# pcb-jetson.net
KiCad netlist of a schematic drawn in EAGLE
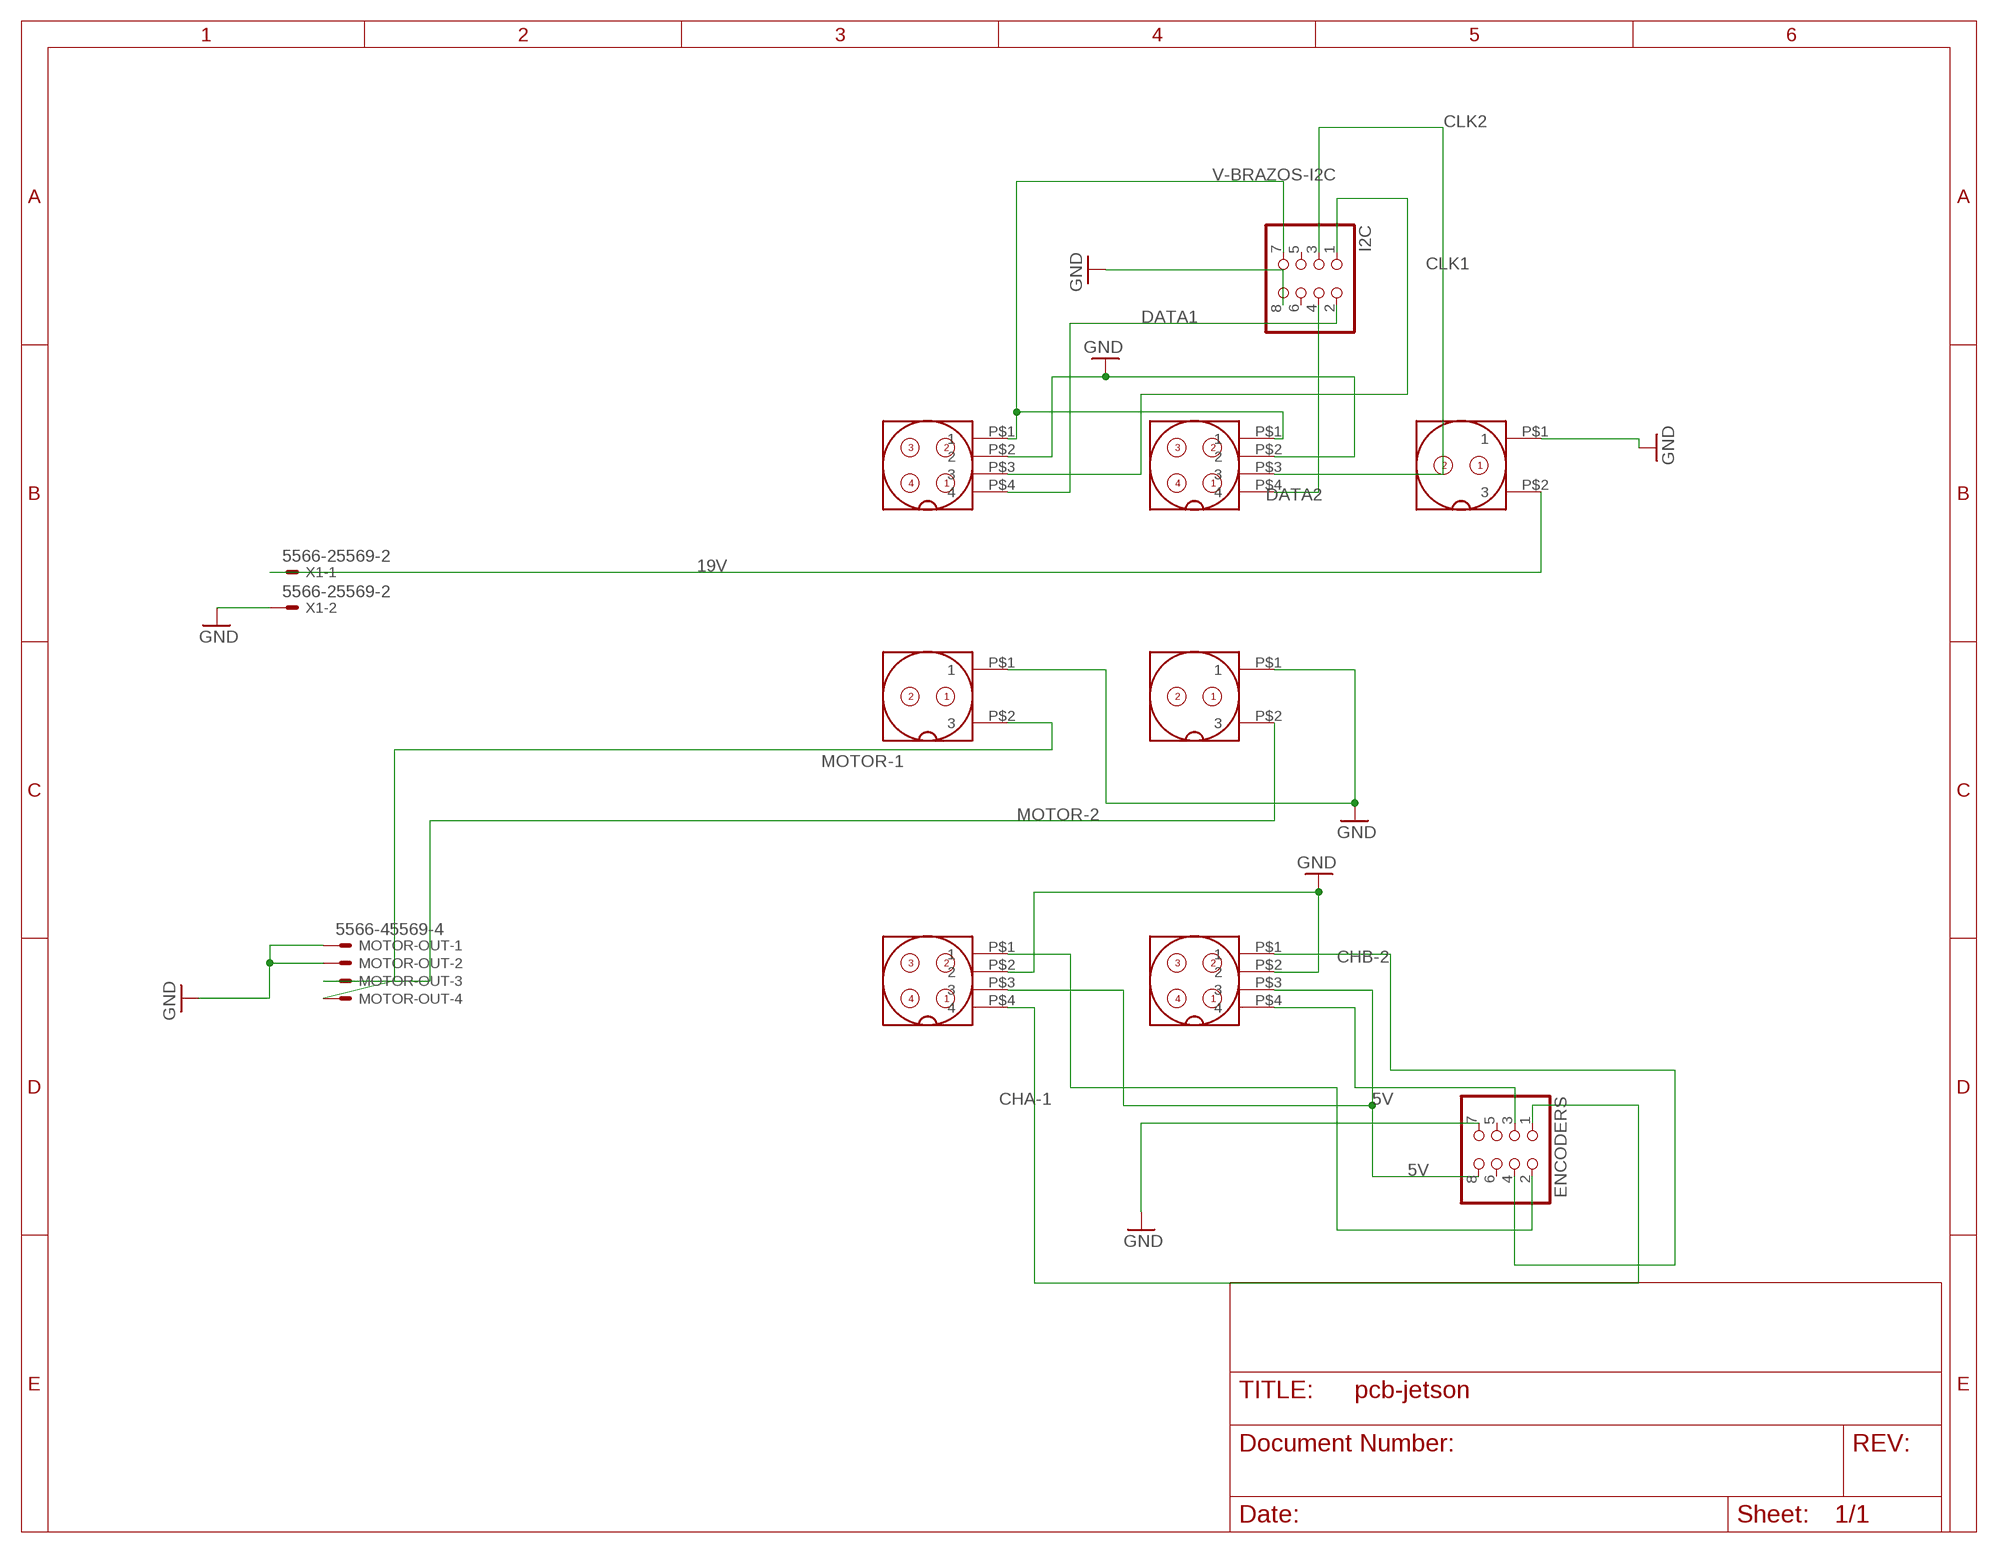
[diagram p0: schematic, sheet 1]

(export (version "E")
  (design (tool "Eeschema 10.0.6"))
  (components
    (comp (ref "BRAZO-I2C-2")
      (value "GX16_4_PINS")
      (footprint "eagle-import:GX16_4_PINS_PADS")
      (libsource (lib "eagle-import") (part "GX16_4_PINS"))
    )
    (comp (ref "BRAZO_I2C-1")
      (value "GX16_4_PINS")
      (footprint "eagle-import:GX16_4_PINS_PADS")
      (libsource (lib "eagle-import") (part "GX16_4_PINS"))
    )
    (comp (ref "ENCODERS")
      (value "PINHD-2X4")
      (footprint "eagle-import:2X04")
      (libsource (lib "eagle-import") (part "PINHD-2X4"))
    )
    (comp (ref "I2C")
      (value "PINHD-2X4")
      (footprint "eagle-import:2X04")
      (libsource (lib "eagle-import") (part "PINHD-2X4"))
    )
    (comp (ref "JETSONIN")
      (value "GX16_2_PINS")
      (footprint "eagle-import:GX16_2_PINS_PADS")
      (libsource (lib "eagle-import") (part "GX16_2_PINS"))
    )
    (comp (ref "MOTOR-OUT")
      (value "5566-45569-4")
      (footprint "eagle-import:5569-4")
      (libsource (lib "eagle-import") (part "5566-45569-4"))
    )
    (comp (ref "MOTOR1")
      (value "GX16_2_PINS")
      (footprint "eagle-import:GX16_2_PINS_PADS")
      (libsource (lib "eagle-import") (part "GX16_2_PINS"))
    )
    (comp (ref "MOTOR2")
      (value "GX16_2_PINS")
      (footprint "eagle-import:GX16_2_PINS_PADS")
      (libsource (lib "eagle-import") (part "GX16_2_PINS"))
    )
    (comp (ref "U$3")
      (value "GX16_4_PINS")
      (footprint "eagle-import:GX16_4_PINS_PADS")
      (libsource (lib "eagle-import") (part "GX16_4_PINS"))
    )
    (comp (ref "U$4")
      (value "GX16_4_PINS")
      (footprint "eagle-import:GX16_4_PINS_PADS")
      (libsource (lib "eagle-import") (part "GX16_4_PINS"))
    )
    (comp (ref "X1")
      (value "5566-25569-2")
      (footprint "eagle-import:5569-2")
      (libsource (lib "eagle-import") (part "5566-25569-2"))
    )
  )
  (nets
    (net (code "1") (name "/5V") (class "Default")
      (node (ref "ENCODERS") (pin "8") (pinfunction "8_8") (pintype "passive"))
      (node (ref "U$3") (pin "P$3") (pinfunction "3_P$3") (pintype "bidirectional"))
      (node (ref "U$4") (pin "P$3") (pinfunction "3_P$3") (pintype "bidirectional"))
    )
    (net (code "2") (name "/19V") (class "Default")
      (node (ref "JETSONIN") (pin "P$2") (pinfunction "3_P$2") (pintype "bidirectional"))
      (node (ref "X1") (pin "1") (pinfunction "S_1") (pintype "passive"))
    )
    (net (code "3") (name "/CHA-1") (class "Default")
      (node (ref "ENCODERS") (pin "1") (pinfunction "1_1") (pintype "passive"))
      (node (ref "U$3") (pin "P$4") (pinfunction "4_P$4") (pintype "bidirectional"))
    )
    (net (code "4") (name "/CHB-2") (class "Default")
      (node (ref "ENCODERS") (pin "4") (pinfunction "4_4") (pintype "passive"))
      (node (ref "U$4") (pin "P$1") (pinfunction "1_P$1") (pintype "bidirectional"))
    )
    (net (code "5") (name "/CLK1") (class "Default")
      (node (ref "BRAZO_I2C-1") (pin "P$3") (pinfunction "3_P$3") (pintype "bidirectional"))
      (node (ref "I2C") (pin "1") (pinfunction "1_1") (pintype "passive"))
    )
    (net (code "6") (name "/CLK2") (class "Default")
      (node (ref "BRAZO-I2C-2") (pin "P$3") (pinfunction "3_P$3") (pintype "bidirectional"))
      (node (ref "I2C") (pin "3") (pinfunction "3_3") (pintype "passive"))
    )
    (net (code "7") (name "/DATA1") (class "Default")
      (node (ref "BRAZO_I2C-1") (pin "P$4") (pinfunction "4_P$4") (pintype "bidirectional"))
      (node (ref "I2C") (pin "2") (pinfunction "2_2") (pintype "passive"))
    )
    (net (code "8") (name "/DATA2") (class "Default")
      (node (ref "BRAZO-I2C-2") (pin "P$4") (pinfunction "4_P$4") (pintype "bidirectional"))
      (node (ref "I2C") (pin "4") (pinfunction "4_4") (pintype "passive"))
    )
    (net (code "9") (name "/MOTOR-1") (class "Default")
      (node (ref "MOTOR-OUT") (pin "4") (pinfunction "S_4") (pintype "passive"))
      (node (ref "MOTOR1") (pin "P$2") (pinfunction "3_P$2") (pintype "bidirectional"))
    )
    (net (code "10") (name "/MOTOR-2") (class "Default")
      (node (ref "MOTOR-OUT") (pin "3") (pinfunction "S_3") (pintype "passive"))
      (node (ref "MOTOR2") (pin "P$2") (pinfunction "3_P$2") (pintype "bidirectional"))
    )
    (net (code "11") (name "/V-BRAZOS-I2C") (class "Default")
      (node (ref "BRAZO-I2C-2") (pin "P$1") (pinfunction "1_P$1") (pintype "bidirectional"))
      (node (ref "BRAZO_I2C-1") (pin "P$1") (pinfunction "1_P$1") (pintype "bidirectional"))
      (node (ref "I2C") (pin "7") (pinfunction "7_7") (pintype "passive"))
    )
    (net (code "12") (name "GND") (class "Default")
      (node (ref "BRAZO-I2C-2") (pin "P$2") (pinfunction "2_P$2") (pintype "bidirectional"))
      (node (ref "BRAZO_I2C-1") (pin "P$2") (pinfunction "2_P$2") (pintype "bidirectional"))
      (node (ref "ENCODERS") (pin "7") (pinfunction "7_7") (pintype "passive"))
      (node (ref "I2C") (pin "8") (pinfunction "8_8") (pintype "passive"))
      (node (ref "JETSONIN") (pin "P$1") (pinfunction "1_P$1") (pintype "bidirectional"))
      (node (ref "MOTOR-OUT") (pin "1") (pinfunction "S_1") (pintype "passive"))
      (node (ref "MOTOR-OUT") (pin "2") (pinfunction "S_2") (pintype "passive"))
      (node (ref "MOTOR1") (pin "P$1") (pinfunction "1_P$1") (pintype "bidirectional"))
      (node (ref "MOTOR2") (pin "P$1") (pinfunction "1_P$1") (pintype "bidirectional"))
      (node (ref "U$3") (pin "P$2") (pinfunction "2_P$2") (pintype "bidirectional"))
      (node (ref "U$4") (pin "P$2") (pinfunction "2_P$2") (pintype "bidirectional"))
      (node (ref "X1") (pin "2") (pinfunction "S_2") (pintype "passive"))
    )
    (net (code "13") (name "Net-(U$3-1)") (class "Default")
      (node (ref "ENCODERS") (pin "2") (pinfunction "2_2") (pintype "passive"))
      (node (ref "U$3") (pin "P$1") (pinfunction "1_P$1") (pintype "bidirectional"))
    )
    (net (code "14") (name "Net-(U$4-4)") (class "Default")
      (node (ref "ENCODERS") (pin "3") (pinfunction "3_3") (pintype "passive"))
      (node (ref "U$4") (pin "P$4") (pinfunction "4_P$4") (pintype "bidirectional"))
    )
    (net (code "15") (name "unconnected-(ENCODERS-Pad5)") (class "Default")
      (node (ref "ENCODERS") (pin "5") (pinfunction "5_5") (pintype "passive"))
    )
    (net (code "16") (name "unconnected-(ENCODERS-Pad6)") (class "Default")
      (node (ref "ENCODERS") (pin "6") (pinfunction "6_6") (pintype "passive"))
    )
    (net (code "17") (name "unconnected-(I2C-Pad5)") (class "Default")
      (node (ref "I2C") (pin "5") (pinfunction "5_5") (pintype "passive"))
    )
    (net (code "18") (name "unconnected-(I2C-Pad6)") (class "Default")
      (node (ref "I2C") (pin "6") (pinfunction "6_6") (pintype "passive"))
    )
  )
)
